# MinipHV4_0.net
KiCad netlist of a schematic drawn in EAGLE
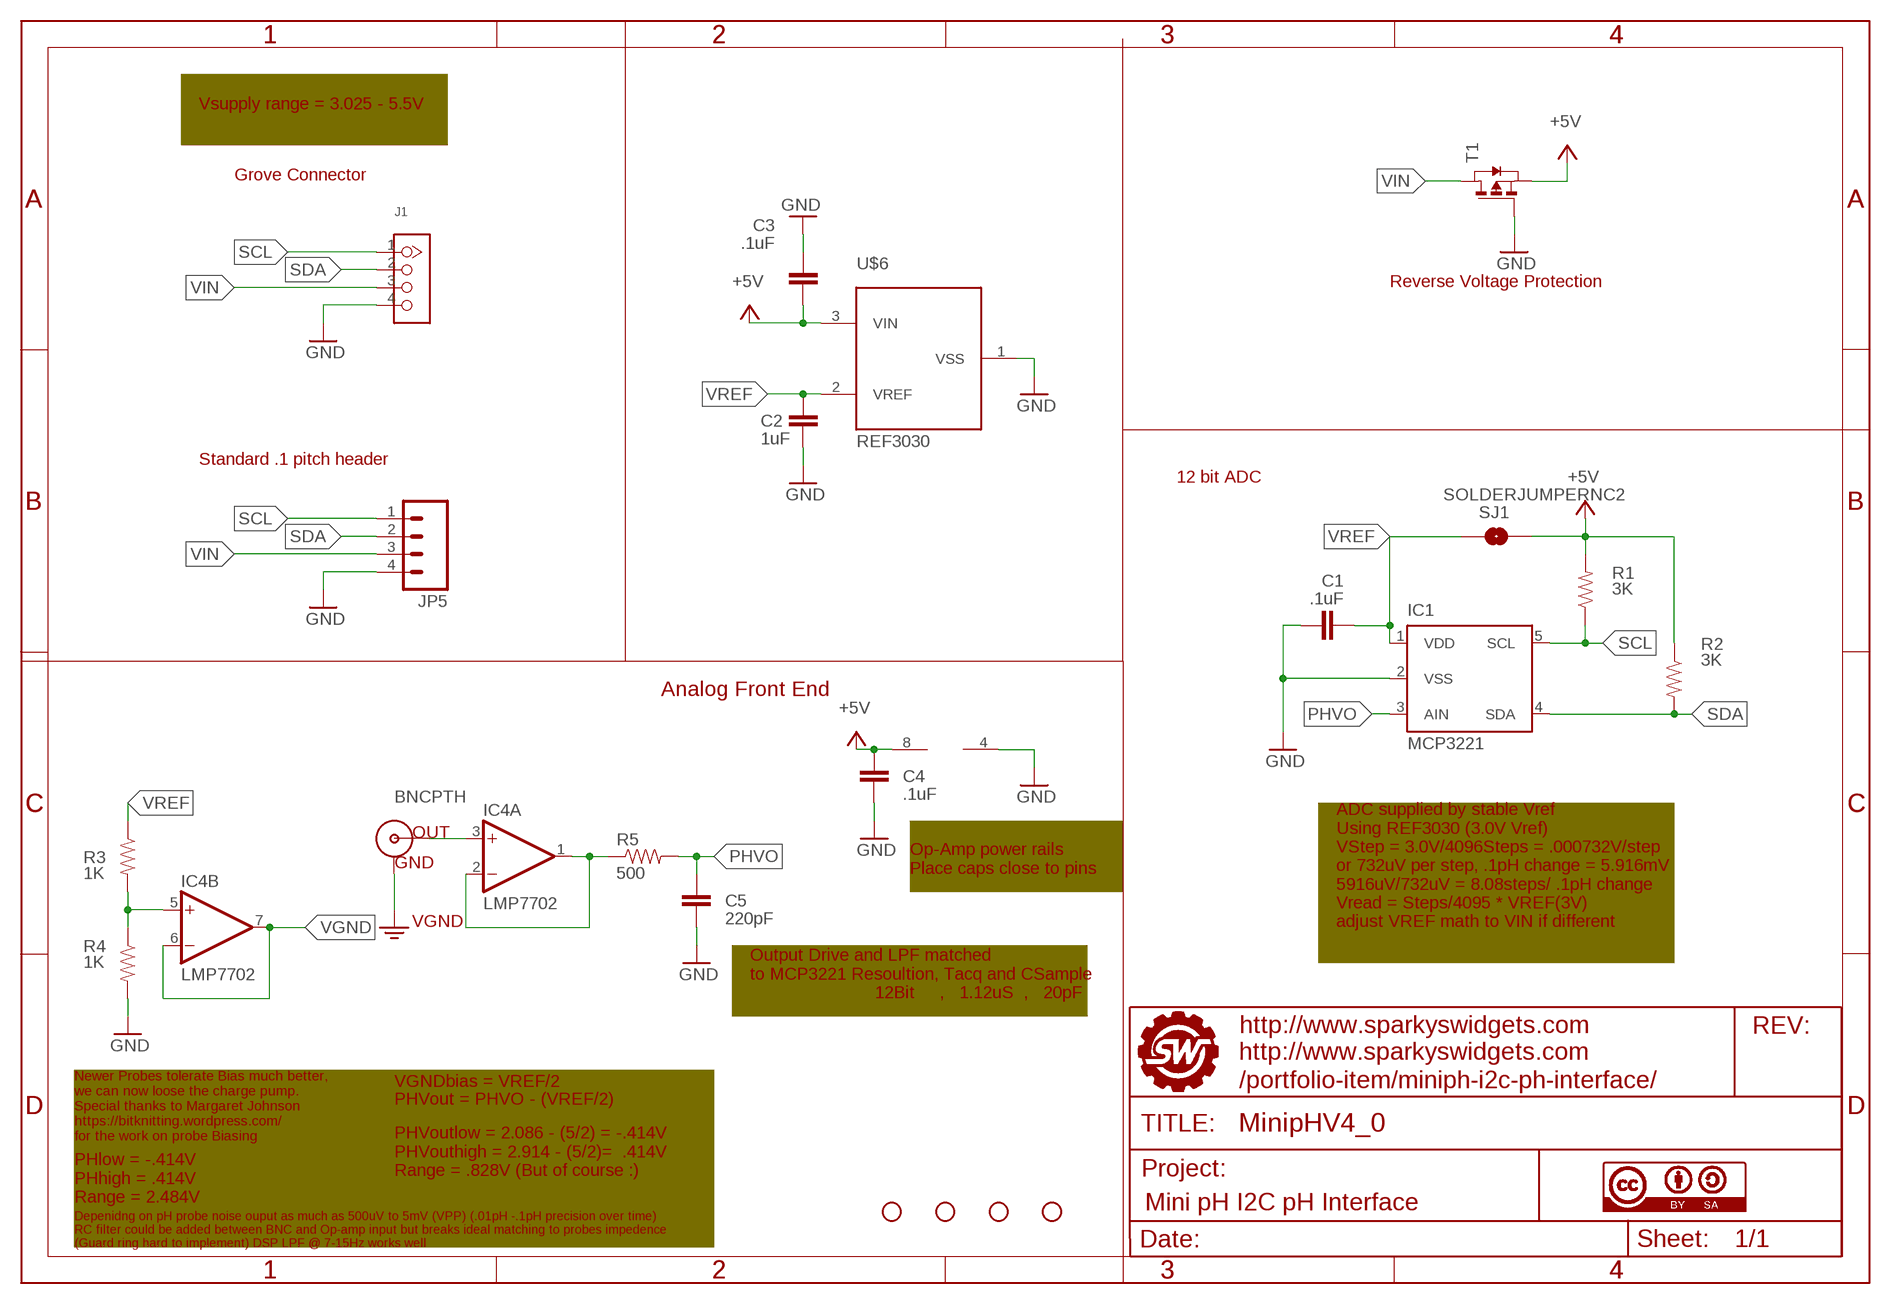
[diagram p0: schematic, sheet 1]

(export (version "E")
  (design (tool "Eeschema 10.0.6"))
  (components
    (comp (ref "C1")
      (value ".1uF")
      (footprint "eagle-import:0805")
      (libsource (lib "eagle-import") (part "CAP0805"))
    )
    (comp (ref "C2")
      (value "1uF")
      (footprint "eagle-import:0805")
      (libsource (lib "eagle-import") (part "CAP0805"))
    )
    (comp (ref "C3")
      (value ".1uF")
      (footprint "eagle-import:0805")
      (libsource (lib "eagle-import") (part "CAP0805"))
    )
    (comp (ref "C4")
      (value ".1uF")
      (footprint "eagle-import:0805")
      (libsource (lib "eagle-import") (part "CAP0805"))
    )
    (comp (ref "C5")
      (value "220pF")
      (footprint "eagle-import:0805")
      (libsource (lib "eagle-import") (part "CAP0805"))
    )
    (comp (ref "IC1")
      (value "MCP3221")
      (footprint "eagle-import:SOT23-DBV")
      (libsource (lib "eagle-import") (part "MCP3221"))
    )
    (comp (ref "IC4")
      (value "LMP7702")
      (footprint "eagle-import:SO08")
      (libsource (lib "eagle-import") (part "LM358D"))
    )
    (comp (ref "J1")
      (value "TWIG-4P-2.0-2.0")
      (footprint "eagle-import:4P-2.0")
      (libsource (lib "eagle-import") (part "TWIG-4P-2.0-2.0"))
    )
    (comp (ref "JP1")
      (value "STAND-OFF")
      (footprint "eagle-import:STAND-OFF")
      (libsource (lib "eagle-import") (part "STAND-OFF"))
    )
    (comp (ref "JP2")
      (value "STAND-OFF")
      (footprint "eagle-import:STAND-OFF")
      (libsource (lib "eagle-import") (part "STAND-OFF"))
    )
    (comp (ref "JP3")
      (value "STAND-OFF")
      (footprint "eagle-import:STAND-OFF")
      (libsource (lib "eagle-import") (part "STAND-OFF"))
    )
    (comp (ref "JP4")
      (value "STAND-OFF")
      (footprint "eagle-import:STAND-OFF")
      (libsource (lib "eagle-import") (part "STAND-OFF"))
    )
    (comp (ref "JP5")
      (value "M04PTH")
      (footprint "eagle-import:1X04")
      (libsource (lib "eagle-import") (part "M04PTH"))
    )
    (comp (ref "R1")
      (value "3K")
      (footprint "eagle-import:0805")
      (libsource (lib "eagle-import") (part "RESISTOR0805-RES"))
    )
    (comp (ref "R2")
      (value "3K")
      (footprint "eagle-import:0805")
      (libsource (lib "eagle-import") (part "RESISTOR0805-RES"))
    )
    (comp (ref "R3")
      (value "1K")
      (footprint "eagle-import:0805")
      (libsource (lib "eagle-import") (part "RESISTOR0805-RES"))
    )
    (comp (ref "R4")
      (value "1K")
      (footprint "eagle-import:0805")
      (libsource (lib "eagle-import") (part "RESISTOR0805-RES"))
    )
    (comp (ref "R5")
      (value "500")
      (footprint "eagle-import:0805")
      (libsource (lib "eagle-import") (part "RESISTOR0805-RES"))
    )
    (comp (ref "SJ1")
      (value "SOLDERJUMPERNC2")
      (footprint "eagle-import:SJ_2S-NOTRACE")
      (libsource (lib "eagle-import") (part "SOLDERJUMPERNC2"))
    )
    (comp (ref "T1")
      (value "PMOSSOT23")
      (footprint "eagle-import:SOT-23")
      (libsource (lib "eagle-import") (part "PMOSSOT23"))
    )
    (comp (ref "U$2")
      (value "BNCPTH")
      (footprint "eagle-import:BNC")
      (libsource (lib "eagle-import") (part "BNCPTH"))
    )
    (comp (ref "U$4")
      (value "FRAME_MINIPH")
      (footprint "eagle-import:SWPCBLOGOWITHINFO")
      (fields
        (field (name "PROJECT") "Mini pH I2C pH Interface")
        (field (name "URL1") "/portfolio-item/miniph-i2c-ph-interface/")
      )
      (libsource (lib "eagle-import") (part "FRAME_MINIPH"))
    )
    (comp (ref "U$5")
      (value "CC-BY-SA")
      (footprint "eagle-import:CC-BY-SA")
      (libsource (lib "eagle-import") (part "CC-BY-SA"))
    )
    (comp (ref "U$6")
      (value "REF3030")
      (footprint "eagle-import:SOT-23")
      (libsource (lib "eagle-import") (part "MCP1541"))
    )
  )
  (nets
    (net (code "1") (name "+5V") (class "Default")
      (node (ref "C3") (pin "1") (pinfunction "1_1") (pintype "passive"))
      (node (ref "C4") (pin "1") (pinfunction "1_1") (pintype "passive"))
      (node (ref "IC4") (pin "8") (pinfunction "V+_8") (pintype "power_in"))
      (node (ref "R1") (pin "2") (pinfunction "2_2") (pintype "passive"))
      (node (ref "R2") (pin "1") (pinfunction "1_1") (pintype "passive"))
      (node (ref "SJ1") (pin "2") (pinfunction "2_2") (pintype "passive"))
      (node (ref "T1") (pin "2") (pinfunction "S_2") (pintype "passive"))
      (node (ref "U$6") (pin "3") (pinfunction "VIN_3") (pintype "power_in"))
    )
    (net (code "2") (name "GND") (class "Default")
      (node (ref "C1") (pin "1") (pinfunction "1_1") (pintype "passive"))
      (node (ref "C2") (pin "2") (pinfunction "2_2") (pintype "passive"))
      (node (ref "C3") (pin "2") (pinfunction "2_2") (pintype "passive"))
      (node (ref "C4") (pin "2") (pinfunction "2_2") (pintype "passive"))
      (node (ref "C5") (pin "2") (pinfunction "2_2") (pintype "passive"))
      (node (ref "IC1") (pin "2") (pinfunction "VSS_2") (pintype "power_in"))
      (node (ref "IC4") (pin "4") (pinfunction "V-_4") (pintype "power_in"))
      (node (ref "J1") (pin "4") (pinfunction "4_4") (pintype "bidirectional"))
      (node (ref "JP5") (pin "4") (pinfunction "4_4") (pintype "passive"))
      (node (ref "R4") (pin "2") (pinfunction "2_2") (pintype "passive"))
      (node (ref "T1") (pin "3") (pinfunction "G_3") (pintype "passive"))
      (node (ref "U$6") (pin "1") (pinfunction "VSS_1") (pintype "power_in"))
    )
    (net (code "3") (name "Net-(IC4A-+IN)") (class "Default")
      (node (ref "IC4") (pin "3") (pinfunction "+IN_3") (pintype "input"))
      (node (ref "U$2") (pin "S") (pinfunction "OUT_S") (pintype "bidirectional"))
    )
    (net (code "4") (name "Net-(IC4A--IN)") (class "Default")
      (node (ref "IC4") (pin "1") (pinfunction "OUT_1") (pintype "output"))
      (node (ref "IC4") (pin "2") (pinfunction "-IN_2") (pintype "input"))
      (node (ref "R5") (pin "1") (pinfunction "1_1") (pintype "passive"))
    )
    (net (code "5") (name "Net-(IC4B-+IN)") (class "Default")
      (node (ref "IC4") (pin "5") (pinfunction "+IN_5") (pintype "input"))
      (node (ref "R3") (pin "2") (pinfunction "2_2") (pintype "passive"))
      (node (ref "R4") (pin "1") (pinfunction "1_1") (pintype "passive"))
    )
    (net (code "6") (name "PHVO") (class "Default")
      (node (ref "C5") (pin "1") (pinfunction "1_1") (pintype "passive"))
      (node (ref "IC1") (pin "3") (pinfunction "AIN_3") (pintype "input"))
      (node (ref "R5") (pin "2") (pinfunction "2_2") (pintype "passive"))
    )
    (net (code "7") (name "SCL") (class "Default")
      (node (ref "IC1") (pin "5") (pinfunction "SCL_5") (pintype "bidirectional"))
      (node (ref "J1") (pin "1") (pinfunction "1_1") (pintype "bidirectional"))
      (node (ref "JP5") (pin "1") (pinfunction "1_1") (pintype "passive"))
      (node (ref "R1") (pin "1") (pinfunction "1_1") (pintype "passive"))
    )
    (net (code "8") (name "SDA") (class "Default")
      (node (ref "IC1") (pin "4") (pinfunction "SDA_4") (pintype "bidirectional"))
      (node (ref "J1") (pin "2") (pinfunction "2_2") (pintype "bidirectional"))
      (node (ref "JP5") (pin "2") (pinfunction "2_2") (pintype "passive"))
      (node (ref "R2") (pin "2") (pinfunction "2_2") (pintype "passive"))
    )
    (net (code "9") (name "VGND") (class "Default")
      (node (ref "IC4") (pin "6") (pinfunction "-IN_6") (pintype "input"))
      (node (ref "IC4") (pin "7") (pinfunction "OUT_7") (pintype "output"))
      (node (ref "U$2") (pin "GND") (pinfunction "GND_GND") (pintype "bidirectional"))
    )
    (net (code "10") (name "VIN") (class "Default")
      (node (ref "J1") (pin "3") (pinfunction "3_3") (pintype "bidirectional"))
      (node (ref "JP5") (pin "3") (pinfunction "3_3") (pintype "passive"))
      (node (ref "T1") (pin "1") (pinfunction "D_1") (pintype "passive"))
    )
    (net (code "11") (name "VREF") (class "Default")
      (node (ref "C1") (pin "2") (pinfunction "2_2") (pintype "passive"))
      (node (ref "C2") (pin "1") (pinfunction "1_1") (pintype "passive"))
      (node (ref "IC1") (pin "1") (pinfunction "VDD_1") (pintype "power_in"))
      (node (ref "R3") (pin "1") (pinfunction "1_1") (pintype "passive"))
      (node (ref "SJ1") (pin "1") (pinfunction "1_1") (pintype "passive"))
      (node (ref "U$6") (pin "2") (pinfunction "VREF_2") (pintype "output"))
    )
  )
)
